# LPCB229_-_TOP.net
KiCad netlist of a schematic drawn in Altium Designer
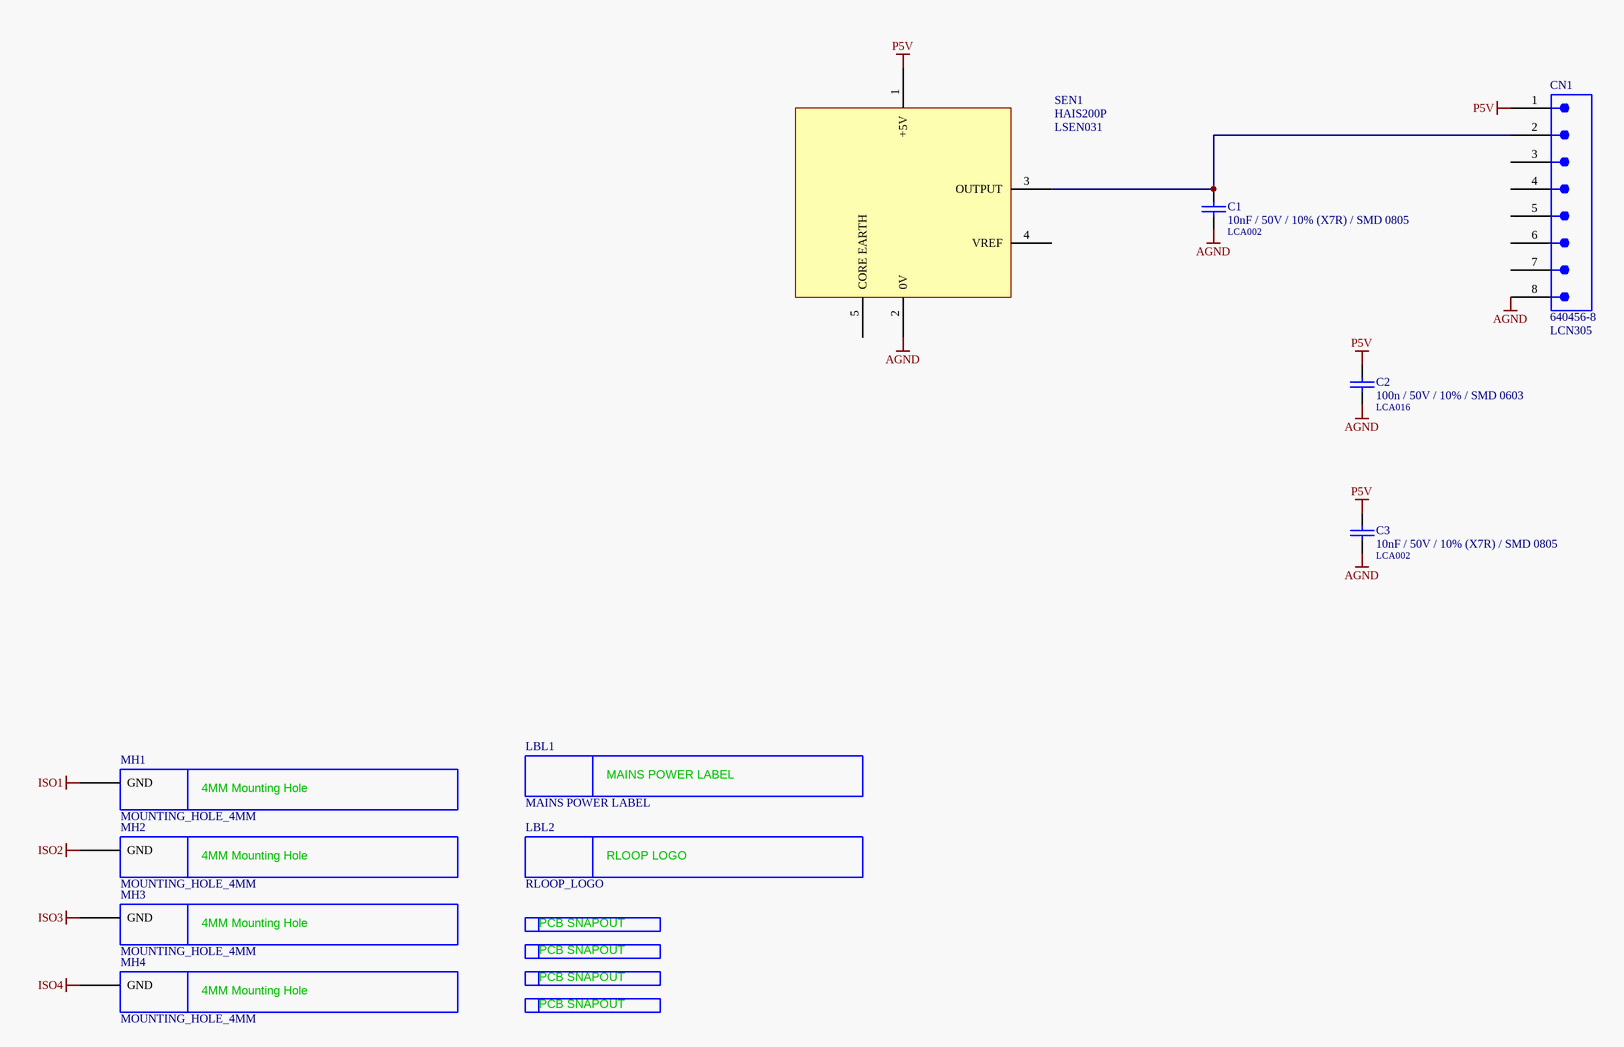
[diagram p0: LPCB229 - TOP.SchDoc]

(export (version "E")
  (design (tool "Eeschema 10.0.6"))
  (components
    (comp (ref "C1")
      (value "10nF / 50V / 10% (X7R) / SMD 0805")
      (footprint "LFP010__CC2012-0805-IPC7351_B")
      (description "Capacitor, Ceramic Chip, 10nF (0.01uF), 50V, 10% (X7R), SMD 0805 [LCA002]")
      (fields (field (name "LDL_NUMBER") "LCA002"))
      (libsource (lib "LDL_Capacitors") (part "10nF / 50V / 10% (X7R) / SMD 0805"))
    )
    (comp (ref "C2")
      (value "100n / 50V / 10% / SMD 0603")
      (footprint "LFP011__CC1608-0603-IPC7351_B")
      (description "Capacitor, Ceramic Chip, 100nF (0.1uF), 50V, 5%, SMD 0603 [LCA016]")
      (fields (field (name "LDL_NUMBER") "LCA016"))
      (libsource (lib "LDL_Capacitors") (part "100n / 50V / 10% / SMD 0603"))
    )
    (comp (ref "C3")
      (value "10nF / 50V / 10% (X7R) / SMD 0805")
      (footprint "LFP010__CC2012-0805-IPC7351_B")
      (description "Capacitor, Ceramic Chip, 10nF (0.01uF), 50V, 10% (X7R), SMD 0805 [LCA002]")
      (fields (field (name "LDL_NUMBER") "LCA002"))
      (libsource (lib "LDL_Capacitors") (part "10nF / 50V / 10% (X7R) / SMD 0805"))
    )
    (comp (ref "CN1")
      (value "640456-8")
      (footprint "640456-8")
      (description "Connector, Male Header, 8 Way")
      (fields (field (name "LDL_NUMBER") "LCN305"))
      (libsource (lib "LDL_Connectors") (part "640456-8"))
    )
    (comp (ref "LBL1")
      (value "MAINS POWER LABEL")
      (footprint "MAINS POWER LABEL")
      (libsource (lib "LDL_Mechanical") (part "MAINS POWER LABEL"))
    )
    (comp (ref "LBL2")
      (value "RLOOP_LOGO")
      (footprint "RLOOP_LOGO")
      (libsource (lib "LDL_Mechanical") (part "RLOOP_LOGO"))
    )
    (comp (ref "MH1")
      (value "MOUNTING_HOLE_4MM")
      (footprint "MOUNTING_HOLE_4MM")
      (description "4MM Mouting Hole")
      (libsource (lib "LDL_Mechanical") (part "MOUNTING_HOLE_4MM"))
    )
    (comp (ref "MH2")
      (value "MOUNTING_HOLE_4MM")
      (footprint "MOUNTING_HOLE_4MM")
      (description "4MM Mouting Hole")
      (libsource (lib "LDL_Mechanical") (part "MOUNTING_HOLE_4MM"))
    )
    (comp (ref "MH3")
      (value "MOUNTING_HOLE_4MM")
      (footprint "MOUNTING_HOLE_4MM")
      (description "4MM Mouting Hole")
      (libsource (lib "LDL_Mechanical") (part "MOUNTING_HOLE_4MM"))
    )
    (comp (ref "MH4")
      (value "MOUNTING_HOLE_4MM")
      (footprint "MOUNTING_HOLE_4MM")
      (description "4MM Mouting Hole")
      (libsource (lib "LDL_Mechanical") (part "MOUNTING_HOLE_4MM"))
    )
    (comp (ref "SEN1")
      (value "HAIS200P")
      (footprint "HAIS200P")
      (description "Hall Current Sensor, 200A Nominal, 600A Max")
      (fields (field (name "LDL_NUMBER") "LSEN031"))
      (libsource (lib "LDL_Sensors_Actuators") (part "HAIS200P"))
    )
    (comp (ref "SN1")
      (value "PCB_SNAPOUT")
      (footprint "SNAPOUT_NEW")
      (libsource (lib "LDL_Mechanical") (part "PCB_SNAPOUT"))
    )
    (comp (ref "SN2")
      (value "PCB_SNAPOUT")
      (footprint "SNAPOUT_NEW")
      (libsource (lib "LDL_Mechanical") (part "PCB_SNAPOUT"))
    )
    (comp (ref "SN3")
      (value "PCB_SNAPOUT")
      (footprint "SNAPOUT_NEW")
      (libsource (lib "LDL_Mechanical") (part "PCB_SNAPOUT"))
    )
    (comp (ref "SN4")
      (value "PCB_SNAPOUT")
      (footprint "SNAPOUT_NEW")
      (libsource (lib "LDL_Mechanical") (part "PCB_SNAPOUT"))
    )
  )
  (nets
    (net (code "1") (name "AGND") (class "Default")
      (node (ref "C1") (pin "2") (pintype "passive"))
      (node (ref "C2") (pin "2") (pintype "passive"))
      (node (ref "C3") (pin "2") (pintype "passive"))
      (node (ref "CN1") (pin "8") (pinfunction "8_8") (pintype "passive"))
      (node (ref "SEN1") (pin "2") (pinfunction "0V_2") (pintype "passive"))
    )
    (net (code "2") (name "ISO1") (class "Default")
      (node (ref "MH1") (pin "MOUNT") (pinfunction "GND_MOUNT") (pintype "passive"))
    )
    (net (code "3") (name "ISO2") (class "Default")
      (node (ref "MH2") (pin "MOUNT") (pinfunction "GND_MOUNT") (pintype "passive"))
    )
    (net (code "4") (name "ISO3") (class "Default")
      (node (ref "MH3") (pin "MOUNT") (pinfunction "GND_MOUNT") (pintype "passive"))
    )
    (net (code "5") (name "ISO4") (class "Default")
      (node (ref "MH4") (pin "MOUNT") (pinfunction "GND_MOUNT") (pintype "passive"))
    )
    (net (code "6") (name "Net-(SEN1-OUTPUT)") (class "Default")
      (node (ref "C1") (pin "1") (pintype "passive"))
      (node (ref "CN1") (pin "2") (pinfunction "2_2") (pintype "passive"))
      (node (ref "SEN1") (pin "3") (pinfunction "OUTPUT_3") (pintype "passive"))
    )
    (net (code "7") (name "P5V") (class "Default")
      (node (ref "C2") (pin "1") (pintype "passive"))
      (node (ref "C3") (pin "1") (pintype "passive"))
      (node (ref "CN1") (pin "1") (pinfunction "1_1") (pintype "passive"))
      (node (ref "SEN1") (pin "1") (pinfunction "+5V_1") (pintype "passive"))
    )
    (net (code "8") (name "unconnected-(CN1-Pad3)") (class "Default")
      (node (ref "CN1") (pin "3") (pinfunction "3_3") (pintype "passive"))
    )
    (net (code "9") (name "unconnected-(CN1-Pad4)") (class "Default")
      (node (ref "CN1") (pin "4") (pinfunction "4_4") (pintype "passive"))
    )
    (net (code "10") (name "unconnected-(CN1-Pad5)") (class "Default")
      (node (ref "CN1") (pin "5") (pinfunction "5_5") (pintype "passive"))
    )
    (net (code "11") (name "unconnected-(CN1-Pad6)") (class "Default")
      (node (ref "CN1") (pin "6") (pinfunction "6_6") (pintype "passive"))
    )
    (net (code "12") (name "unconnected-(CN1-Pad7)") (class "Default")
      (node (ref "CN1") (pin "7") (pinfunction "7_7") (pintype "passive"))
    )
    (net (code "13") (name "unconnected-(SEN1-CORE_EARTH-Pad5)") (class "Default")
      (node (ref "SEN1") (pin "5") (pinfunction "CORE_EARTH_5") (pintype "passive"))
    )
    (net (code "14") (name "unconnected-(SEN1-VREF-Pad4)") (class "Default")
      (node (ref "SEN1") (pin "4") (pinfunction "VREF_4") (pintype "passive"))
    )
  )
)
